# BMSMAX14921Based.net
KiCad netlist of a schematic drawn in EAGLE
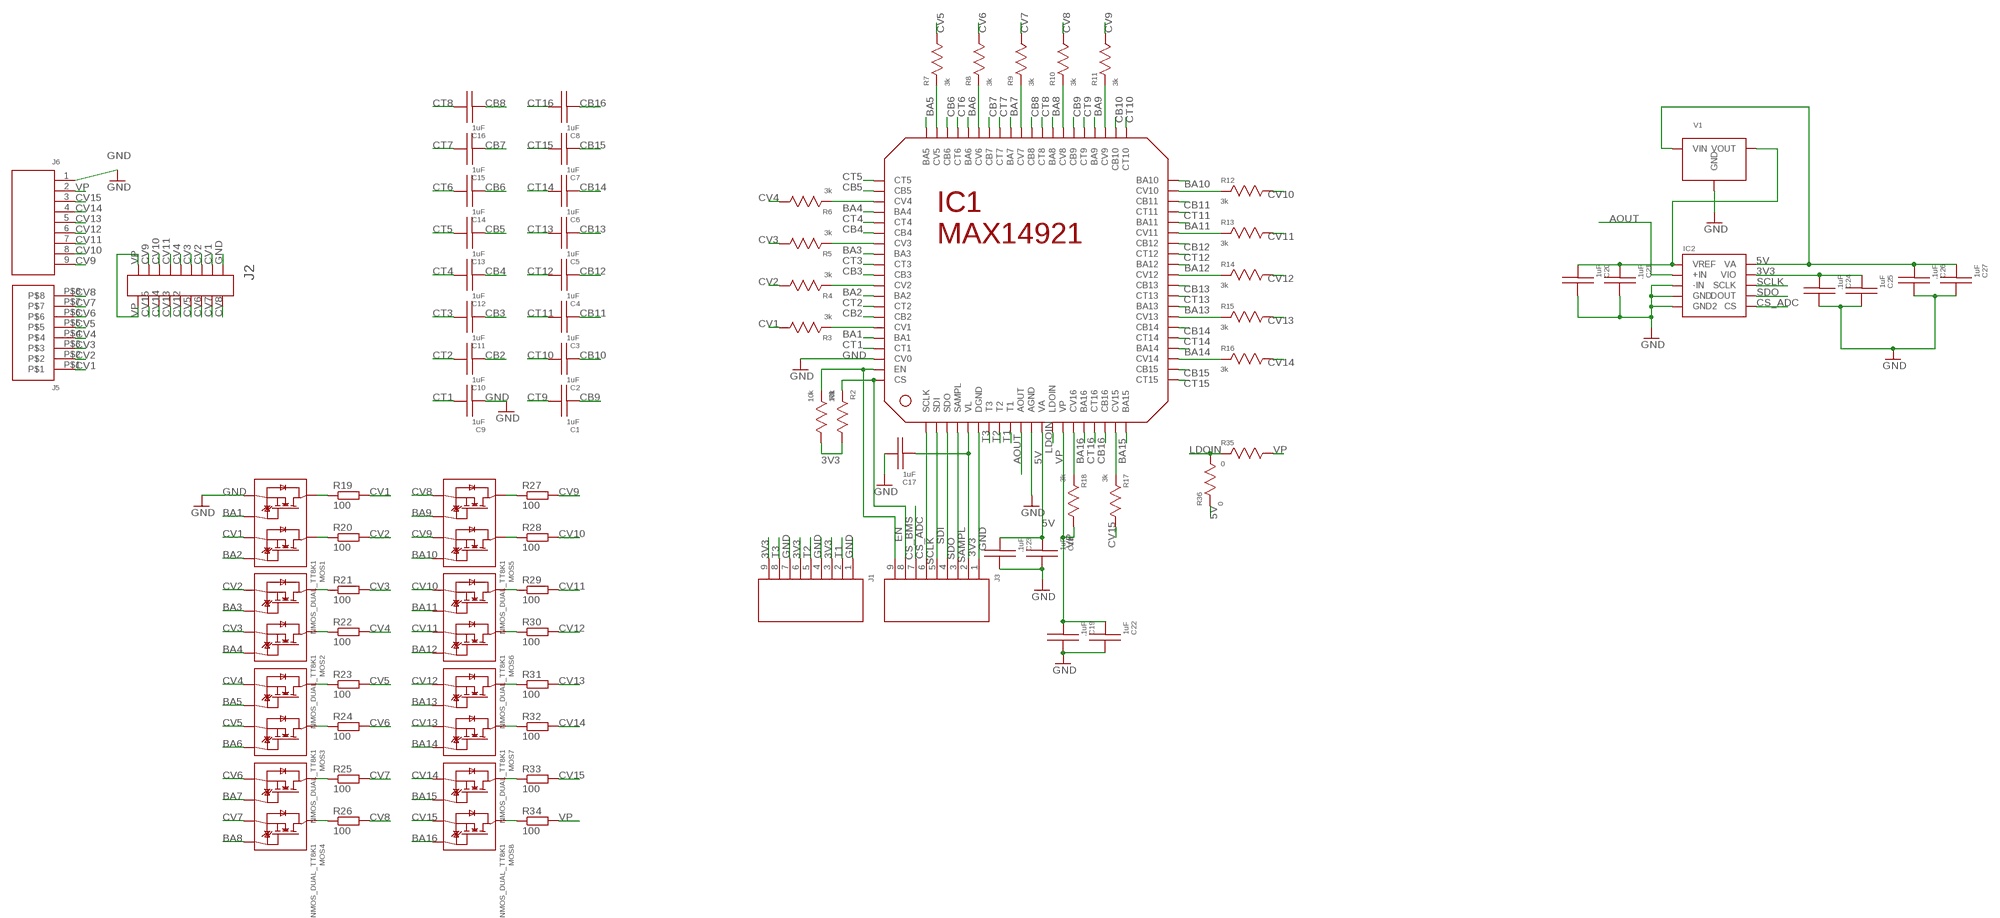
[diagram p0: schematic, sheet 1]

(export (version "E")
  (design (tool "Eeschema 10.0.6"))
  (components
    (comp (ref "C1")
      (value "1uF")
      (footprint "eagle-import:0805_(2012_METRIC)")
      (libsource (lib "eagle-import") (part "CHIP_CAP0805"))
    )
    (comp (ref "C2")
      (value "1uF")
      (footprint "eagle-import:0805_(2012_METRIC)")
      (libsource (lib "eagle-import") (part "CHIP_CAP0805"))
    )
    (comp (ref "C3")
      (value "1uF")
      (footprint "eagle-import:0805_(2012_METRIC)")
      (libsource (lib "eagle-import") (part "CHIP_CAP0805"))
    )
    (comp (ref "C4")
      (value "1uF")
      (footprint "eagle-import:0805_(2012_METRIC)")
      (libsource (lib "eagle-import") (part "CHIP_CAP0805"))
    )
    (comp (ref "C5")
      (value "1uF")
      (footprint "eagle-import:0805_(2012_METRIC)")
      (libsource (lib "eagle-import") (part "CHIP_CAP0805"))
    )
    (comp (ref "C6")
      (value "1uF")
      (footprint "eagle-import:0805_(2012_METRIC)")
      (libsource (lib "eagle-import") (part "CHIP_CAP0805"))
    )
    (comp (ref "C7")
      (value "1uF")
      (footprint "eagle-import:0805_(2012_METRIC)")
      (libsource (lib "eagle-import") (part "CHIP_CAP0805"))
    )
    (comp (ref "C8")
      (value "1uF")
      (footprint "eagle-import:0805_(2012_METRIC)")
      (libsource (lib "eagle-import") (part "CHIP_CAP0805"))
    )
    (comp (ref "C9")
      (value "1uF")
      (footprint "eagle-import:0805_(2012_METRIC)")
      (libsource (lib "eagle-import") (part "CHIP_CAP0805"))
    )
    (comp (ref "C10")
      (value "1uF")
      (footprint "eagle-import:0805_(2012_METRIC)")
      (libsource (lib "eagle-import") (part "CHIP_CAP0805"))
    )
    (comp (ref "C11")
      (value "1uF")
      (footprint "eagle-import:0805_(2012_METRIC)")
      (libsource (lib "eagle-import") (part "CHIP_CAP0805"))
    )
    (comp (ref "C12")
      (value "1uF")
      (footprint "eagle-import:0805_(2012_METRIC)")
      (libsource (lib "eagle-import") (part "CHIP_CAP0805"))
    )
    (comp (ref "C13")
      (value "1uF")
      (footprint "eagle-import:0805_(2012_METRIC)")
      (libsource (lib "eagle-import") (part "CHIP_CAP0805"))
    )
    (comp (ref "C14")
      (value "1uF")
      (footprint "eagle-import:0805_(2012_METRIC)")
      (libsource (lib "eagle-import") (part "CHIP_CAP0805"))
    )
    (comp (ref "C15")
      (value "1uF")
      (footprint "eagle-import:0805_(2012_METRIC)")
      (libsource (lib "eagle-import") (part "CHIP_CAP0805"))
    )
    (comp (ref "C16")
      (value "1uF")
      (footprint "eagle-import:0805_(2012_METRIC)")
      (libsource (lib "eagle-import") (part "CHIP_CAP0805"))
    )
    (comp (ref "C17")
      (value "1uF")
      (footprint "eagle-import:0805_(2012_METRIC)")
      (libsource (lib "eagle-import") (part "CHIP_CAP0805"))
    )
    (comp (ref "C18")
      (value "1uF")
      (footprint "eagle-import:0805_(2012_METRIC)")
      (libsource (lib "eagle-import") (part "CHIP_CAP0805"))
    )
    (comp (ref "C19")
      (value ".1uF")
      (footprint "eagle-import:0805_(2012_METRIC)")
      (libsource (lib "eagle-import") (part "CHIP_CAP0805"))
    )
    (comp (ref "C20")
      (value "1uF")
      (footprint "eagle-import:0805_(2012_METRIC)")
      (libsource (lib "eagle-import") (part "CHIP_CAP0805"))
    )
    (comp (ref "C21")
      (value ".1uF")
      (footprint "eagle-import:0805_(2012_METRIC)")
      (libsource (lib "eagle-import") (part "CHIP_CAP0805"))
    )
    (comp (ref "C22")
      (value "1uF")
      (footprint "eagle-import:0805_(2012_METRIC)")
      (libsource (lib "eagle-import") (part "CHIP_CAP0805"))
    )
    (comp (ref "C23")
      (value ".1uF")
      (footprint "eagle-import:0805_(2012_METRIC)")
      (libsource (lib "eagle-import") (part "CHIP_CAP0805"))
    )
    (comp (ref "C24")
      (value ".1uF")
      (footprint "eagle-import:0805_(2012_METRIC)")
      (libsource (lib "eagle-import") (part "CHIP_CAP0805"))
    )
    (comp (ref "C25")
      (value "1uF")
      (footprint "eagle-import:0805_(2012_METRIC)")
      (libsource (lib "eagle-import") (part "CHIP_CAP0805"))
    )
    (comp (ref "C26")
      (value ".1uF")
      (footprint "eagle-import:0805_(2012_METRIC)")
      (libsource (lib "eagle-import") (part "CHIP_CAP0805"))
    )
    (comp (ref "C27")
      (value "1uF")
      (footprint "eagle-import:0805_(2012_METRIC)")
      (libsource (lib "eagle-import") (part "CHIP_CAP0805"))
    )
    (comp (ref "IC1")
      (value "MAX14921")
      (footprint "eagle-import:80TQFP")
      (libsource (lib "eagle-import") (part "MAX14921"))
    )
    (comp (ref "IC2")
      (value "ADC141S626")
      (footprint "eagle-import:10-VSSOP")
      (libsource (lib "eagle-import") (part "ADC141S626"))
    )
    (comp (ref "J1")
      (value "CONNECTOR_9PIN")
      (footprint "eagle-import:9PIN_.1'")
      (libsource (lib "eagle-import") (part "CONNECTOR_9PIN"))
    )
    (comp (ref "J2")
      (value "CONNECTORJST2X9_2MM")
      (footprint "eagle-import:CONNECTOR9X2_2MMPITCH")
      (libsource (lib "eagle-import") (part "CONNECTORJST2X9_2MM"))
    )
    (comp (ref "J3")
      (value "CONNECTOR_9PIN")
      (footprint "eagle-import:9PIN_.1'")
      (libsource (lib "eagle-import") (part "CONNECTOR_9PIN"))
    )
    (comp (ref "J5")
      (value "CONNECTOR_8PIN")
      (footprint "eagle-import:8PIN_.1'")
      (libsource (lib "eagle-import") (part "CONNECTOR_8PIN"))
    )
    (comp (ref "J6")
      (value "CONNECTOR_9PIN")
      (footprint "eagle-import:9PIN_.1'")
      (libsource (lib "eagle-import") (part "CONNECTOR_9PIN"))
    )
    (comp (ref "MOS1")
      (value "NMOS_DUAL_TT8K1")
      (footprint "eagle-import:TSST8")
      (libsource (lib "eagle-import") (part "NMOS_DUAL_TT8K1"))
    )
    (comp (ref "MOS2")
      (value "NMOS_DUAL_TT8K1")
      (footprint "eagle-import:TSST8")
      (libsource (lib "eagle-import") (part "NMOS_DUAL_TT8K1"))
    )
    (comp (ref "MOS3")
      (value "NMOS_DUAL_TT8K1")
      (footprint "eagle-import:TSST8")
      (libsource (lib "eagle-import") (part "NMOS_DUAL_TT8K1"))
    )
    (comp (ref "MOS4")
      (value "NMOS_DUAL_TT8K1")
      (footprint "eagle-import:TSST8")
      (libsource (lib "eagle-import") (part "NMOS_DUAL_TT8K1"))
    )
    (comp (ref "MOS5")
      (value "NMOS_DUAL_TT8K1")
      (footprint "eagle-import:TSST8")
      (libsource (lib "eagle-import") (part "NMOS_DUAL_TT8K1"))
    )
    (comp (ref "MOS6")
      (value "NMOS_DUAL_TT8K1")
      (footprint "eagle-import:TSST8")
      (libsource (lib "eagle-import") (part "NMOS_DUAL_TT8K1"))
    )
    (comp (ref "MOS7")
      (value "NMOS_DUAL_TT8K1")
      (footprint "eagle-import:TSST8")
      (libsource (lib "eagle-import") (part "NMOS_DUAL_TT8K1"))
    )
    (comp (ref "MOS8")
      (value "NMOS_DUAL_TT8K1")
      (footprint "eagle-import:TSST8")
      (libsource (lib "eagle-import") (part "NMOS_DUAL_TT8K1"))
    )
    (comp (ref "R1")
      (value "10k")
      (footprint "eagle-import:0805_(2012_METRIC)")
      (libsource (lib "eagle-import") (part "CHIP_RES0805"))
    )
    (comp (ref "R2")
      (value "10k")
      (footprint "eagle-import:0805_(2012_METRIC)")
      (libsource (lib "eagle-import") (part "CHIP_RES0805"))
    )
    (comp (ref "R3")
      (value "3k")
      (footprint "eagle-import:0805_(2012_METRIC)")
      (libsource (lib "eagle-import") (part "CHIP_RES0805"))
    )
    (comp (ref "R4")
      (value "3k")
      (footprint "eagle-import:0805_(2012_METRIC)")
      (libsource (lib "eagle-import") (part "CHIP_RES0805"))
    )
    (comp (ref "R5")
      (value "3k")
      (footprint "eagle-import:0805_(2012_METRIC)")
      (libsource (lib "eagle-import") (part "CHIP_RES0805"))
    )
    (comp (ref "R6")
      (value "3k")
      (footprint "eagle-import:0805_(2012_METRIC)")
      (libsource (lib "eagle-import") (part "CHIP_RES0805"))
    )
    (comp (ref "R7")
      (value "3k")
      (footprint "eagle-import:0805_(2012_METRIC)")
      (libsource (lib "eagle-import") (part "CHIP_RES0805"))
    )
    (comp (ref "R8")
      (value "3k")
      (footprint "eagle-import:0805_(2012_METRIC)")
      (libsource (lib "eagle-import") (part "CHIP_RES0805"))
    )
    (comp (ref "R9")
      (value "3k")
      (footprint "eagle-import:0805_(2012_METRIC)")
      (libsource (lib "eagle-import") (part "CHIP_RES0805"))
    )
    (comp (ref "R10")
      (value "3k")
      (footprint "eagle-import:0805_(2012_METRIC)")
      (libsource (lib "eagle-import") (part "CHIP_RES0805"))
    )
    (comp (ref "R11")
      (value "3k")
      (footprint "eagle-import:0805_(2012_METRIC)")
      (libsource (lib "eagle-import") (part "CHIP_RES0805"))
    )
    (comp (ref "R12")
      (value "3k")
      (footprint "eagle-import:0805_(2012_METRIC)")
      (libsource (lib "eagle-import") (part "CHIP_RES0805"))
    )
    (comp (ref "R13")
      (value "3k")
      (footprint "eagle-import:0805_(2012_METRIC)")
      (libsource (lib "eagle-import") (part "CHIP_RES0805"))
    )
    (comp (ref "R14")
      (value "3k")
      (footprint "eagle-import:0805_(2012_METRIC)")
      (libsource (lib "eagle-import") (part "CHIP_RES0805"))
    )
    (comp (ref "R15")
      (value "3k")
      (footprint "eagle-import:0805_(2012_METRIC)")
      (libsource (lib "eagle-import") (part "CHIP_RES0805"))
    )
    (comp (ref "R16")
      (value "3k")
      (footprint "eagle-import:0805_(2012_METRIC)")
      (libsource (lib "eagle-import") (part "CHIP_RES0805"))
    )
    (comp (ref "R17")
      (value "3k")
      (footprint "eagle-import:0805_(2012_METRIC)")
      (libsource (lib "eagle-import") (part "CHIP_RES0805"))
    )
    (comp (ref "R18")
      (value "3k")
      (footprint "eagle-import:0805_(2012_METRIC)")
      (libsource (lib "eagle-import") (part "CHIP_RES0805"))
    )
    (comp (ref "R19")
      (value "100")
      (footprint "eagle-import:0411V")
      (libsource (lib "eagle-import") (part "R-EU_0411/3V"))
    )
    (comp (ref "R20")
      (value "100")
      (footprint "eagle-import:0411V")
      (libsource (lib "eagle-import") (part "R-EU_0411/3V"))
    )
    (comp (ref "R21")
      (value "100")
      (footprint "eagle-import:0411V")
      (libsource (lib "eagle-import") (part "R-EU_0411/3V"))
    )
    (comp (ref "R22")
      (value "100")
      (footprint "eagle-import:0411V")
      (libsource (lib "eagle-import") (part "R-EU_0411/3V"))
    )
    (comp (ref "R23")
      (value "100")
      (footprint "eagle-import:0411V")
      (libsource (lib "eagle-import") (part "R-EU_0411/3V"))
    )
    (comp (ref "R24")
      (value "100")
      (footprint "eagle-import:0411V")
      (libsource (lib "eagle-import") (part "R-EU_0411/3V"))
    )
    (comp (ref "R25")
      (value "100")
      (footprint "eagle-import:0411V")
      (libsource (lib "eagle-import") (part "R-EU_0411/3V"))
    )
    (comp (ref "R26")
      (value "100")
      (footprint "eagle-import:0411V")
      (libsource (lib "eagle-import") (part "R-EU_0411/3V"))
    )
    (comp (ref "R27")
      (value "100")
      (footprint "eagle-import:0411V")
      (libsource (lib "eagle-import") (part "R-EU_0411/3V"))
    )
    (comp (ref "R28")
      (value "100")
      (footprint "eagle-import:0411V")
      (libsource (lib "eagle-import") (part "R-EU_0411/3V"))
    )
    (comp (ref "R29")
      (value "100")
      (footprint "eagle-import:0411V")
      (libsource (lib "eagle-import") (part "R-EU_0411/3V"))
    )
    (comp (ref "R30")
      (value "100")
      (footprint "eagle-import:0411V")
      (libsource (lib "eagle-import") (part "R-EU_0411/3V"))
    )
    (comp (ref "R31")
      (value "100")
      (footprint "eagle-import:0411V")
      (libsource (lib "eagle-import") (part "R-EU_0411/3V"))
    )
    (comp (ref "R32")
      (value "100")
      (footprint "eagle-import:0411V")
      (libsource (lib "eagle-import") (part "R-EU_0411/3V"))
    )
    (comp (ref "R33")
      (value "100")
      (footprint "eagle-import:0411V")
      (libsource (lib "eagle-import") (part "R-EU_0411/3V"))
    )
    (comp (ref "R34")
      (value "100")
      (footprint "eagle-import:0411V")
      (libsource (lib "eagle-import") (part "R-EU_0411/3V"))
    )
    (comp (ref "R35")
      (value "0")
      (footprint "eagle-import:0805_(2012_METRIC)")
      (libsource (lib "eagle-import") (part "CHIP_RES0805"))
    )
    (comp (ref "R36")
      (value "0")
      (footprint "eagle-import:0805_(2012_METRIC)")
      (libsource (lib "eagle-import") (part "CHIP_RES0805"))
    )
    (comp (ref "V1")
      (value "REF3040")
      (footprint "eagle-import:SOT-23")
      (libsource (lib "eagle-import") (part "REF3040"))
    )
  )
  (nets
    (net (code "1") (name "/3V3") (class "Default")
      (node (ref "C17") (pin "P$2") (pinfunction "P$1_P$2") (pintype "bidirectional"))
      (node (ref "C24") (pin "P$2") (pinfunction "P$1_P$2") (pintype "bidirectional"))
      (node (ref "C25") (pin "P$2") (pinfunction "P$1_P$2") (pintype "bidirectional"))
      (node (ref "IC1") (pin "P$5") (pinfunction "VL_P$5") (pintype "bidirectional"))
      (node (ref "IC2") (pin "P$9") (pinfunction "VIO_P$9") (pintype "bidirectional"))
      (node (ref "J1") (pin "3") (pinfunction "P$3_3") (pintype "bidirectional"))
      (node (ref "J1") (pin "6") (pinfunction "P$6_6") (pintype "bidirectional"))
      (node (ref "J1") (pin "9") (pinfunction "P$9_9") (pintype "bidirectional"))
      (node (ref "J3") (pin "2") (pinfunction "P$2_2") (pintype "bidirectional"))
      (node (ref "R1") (pin "P$1") (pinfunction "P$2_P$1") (pintype "bidirectional"))
      (node (ref "R2") (pin "P$1") (pinfunction "P$2_P$1") (pintype "bidirectional"))
    )
    (net (code "2") (name "/5V") (class "Default")
      (node (ref "C18") (pin "P$2") (pinfunction "P$1_P$2") (pintype "bidirectional"))
      (node (ref "C23") (pin "P$2") (pinfunction "P$1_P$2") (pintype "bidirectional"))
      (node (ref "C26") (pin "P$2") (pinfunction "P$1_P$2") (pintype "bidirectional"))
      (node (ref "C27") (pin "P$2") (pinfunction "P$1_P$2") (pintype "bidirectional"))
      (node (ref "IC1") (pin "P$12") (pinfunction "VA_P$12") (pintype "bidirectional"))
      (node (ref "IC2") (pin "P$10") (pinfunction "VA_P$10") (pintype "bidirectional"))
      (node (ref "R36") (pin "P$2") (pinfunction "P$1_P$2") (pintype "bidirectional"))
      (node (ref "V1") (pin "1") (pinfunction "VIN_1") (pintype "bidirectional"))
    )
    (net (code "3") (name "/AOUT") (class "Default")
      (node (ref "IC1") (pin "P$10") (pinfunction "AOUT_P$10") (pintype "bidirectional"))
      (node (ref "IC2") (pin "P$2") (pinfunction "+IN_P$2") (pintype "bidirectional"))
    )
    (net (code "4") (name "/BA1") (class "Default")
      (node (ref "IC1") (pin "P$76") (pinfunction "BA1_P$76") (pintype "bidirectional"))
      (node (ref "MOS1") (pin "P$2") (pinfunction "G1_P$2") (pintype "bidirectional"))
    )
    (net (code "5") (name "/BA2") (class "Default")
      (node (ref "IC1") (pin "P$72") (pinfunction "BA2_P$72") (pintype "bidirectional"))
      (node (ref "MOS1") (pin "P$4") (pinfunction "G2_P$4") (pintype "bidirectional"))
    )
    (net (code "6") (name "/BA3") (class "Default")
      (node (ref "IC1") (pin "P$68") (pinfunction "BA3_P$68") (pintype "bidirectional"))
      (node (ref "MOS2") (pin "P$2") (pinfunction "G1_P$2") (pintype "bidirectional"))
    )
    (net (code "7") (name "/BA4") (class "Default")
      (node (ref "IC1") (pin "P$64") (pinfunction "BA4_P$64") (pintype "bidirectional"))
      (node (ref "MOS2") (pin "P$4") (pinfunction "G2_P$4") (pintype "bidirectional"))
    )
    (net (code "8") (name "/BA5") (class "Default")
      (node (ref "IC1") (pin "P$60") (pinfunction "BA5_P$60") (pintype "bidirectional"))
      (node (ref "MOS3") (pin "P$2") (pinfunction "G1_P$2") (pintype "bidirectional"))
    )
    (net (code "9") (name "/BA6") (class "Default")
      (node (ref "IC1") (pin "P$56") (pinfunction "BA6_P$56") (pintype "bidirectional"))
      (node (ref "MOS3") (pin "P$4") (pinfunction "G2_P$4") (pintype "bidirectional"))
    )
    (net (code "10") (name "/BA7") (class "Default")
      (node (ref "IC1") (pin "P$52") (pinfunction "BA7_P$52") (pintype "bidirectional"))
      (node (ref "MOS4") (pin "P$2") (pinfunction "G1_P$2") (pintype "bidirectional"))
    )
    (net (code "11") (name "/BA8") (class "Default")
      (node (ref "IC1") (pin "P$48") (pinfunction "BA8_P$48") (pintype "bidirectional"))
      (node (ref "MOS4") (pin "P$4") (pinfunction "G2_P$4") (pintype "bidirectional"))
    )
    (net (code "12") (name "/BA9") (class "Default")
      (node (ref "IC1") (pin "P$44") (pinfunction "BA9_P$44") (pintype "bidirectional"))
      (node (ref "MOS5") (pin "P$2") (pinfunction "G1_P$2") (pintype "bidirectional"))
    )
    (net (code "13") (name "/BA10") (class "Default")
      (node (ref "IC1") (pin "P$40") (pinfunction "BA10_P$40") (pintype "bidirectional"))
      (node (ref "MOS5") (pin "P$4") (pinfunction "G2_P$4") (pintype "bidirectional"))
    )
    (net (code "14") (name "/BA11") (class "Default")
      (node (ref "IC1") (pin "P$36") (pinfunction "BA11_P$36") (pintype "bidirectional"))
      (node (ref "MOS6") (pin "P$2") (pinfunction "G1_P$2") (pintype "bidirectional"))
    )
    (net (code "15") (name "/BA12") (class "Default")
      (node (ref "IC1") (pin "P$32") (pinfunction "BA12_P$32") (pintype "bidirectional"))
      (node (ref "MOS6") (pin "P$4") (pinfunction "G2_P$4") (pintype "bidirectional"))
    )
    (net (code "16") (name "/BA13") (class "Default")
      (node (ref "IC1") (pin "P$28") (pinfunction "BA13_P$28") (pintype "bidirectional"))
      (node (ref "MOS7") (pin "P$2") (pinfunction "G1_P$2") (pintype "bidirectional"))
    )
    (net (code "17") (name "/BA14") (class "Default")
      (node (ref "IC1") (pin "P$24") (pinfunction "BA14_P$24") (pintype "bidirectional"))
      (node (ref "MOS7") (pin "P$4") (pinfunction "G2_P$4") (pintype "bidirectional"))
    )
    (net (code "18") (name "/BA15") (class "Default")
      (node (ref "IC1") (pin "P$20") (pinfunction "BA15_P$20") (pintype "bidirectional"))
      (node (ref "MOS8") (pin "P$2") (pinfunction "G1_P$2") (pintype "bidirectional"))
    )
    (net (code "19") (name "/BA16") (class "Default")
      (node (ref "IC1") (pin "P$16") (pinfunction "BA16_P$16") (pintype "bidirectional"))
      (node (ref "MOS8") (pin "P$4") (pinfunction "G2_P$4") (pintype "bidirectional"))
    )
    (net (code "20") (name "/CB2") (class "Default")
      (node (ref "C10") (pin "P$2") (pinfunction "P$1_P$2") (pintype "bidirectional"))
      (node (ref "IC1") (pin "P$74") (pinfunction "CB2_P$74") (pintype "bidirectional"))
    )
    (net (code "21") (name "/CB3") (class "Default")
      (node (ref "C11") (pin "P$2") (pinfunction "P$1_P$2") (pintype "bidirectional"))
      (node (ref "IC1") (pin "P$70") (pinfunction "CB3_P$70") (pintype "bidirectional"))
    )
    (net (code "22") (name "/CB4") (class "Default")
      (node (ref "C12") (pin "P$2") (pinfunction "P$1_P$2") (pintype "bidirectional"))
      (node (ref "IC1") (pin "P$66") (pinfunction "CB4_P$66") (pintype "bidirectional"))
    )
    (net (code "23") (name "/CB5") (class "Default")
      (node (ref "C13") (pin "P$2") (pinfunction "P$1_P$2") (pintype "bidirectional"))
      (node (ref "IC1") (pin "P$62") (pinfunction "CB5_P$62") (pintype "bidirectional"))
    )
    (net (code "24") (name "/CB6") (class "Default")
      (node (ref "C14") (pin "P$2") (pinfunction "P$1_P$2") (pintype "bidirectional"))
      (node (ref "IC1") (pin "P$58") (pinfunction "CB6_P$58") (pintype "bidirectional"))
    )
    (net (code "25") (name "/CB7") (class "Default")
      (node (ref "C15") (pin "P$2") (pinfunction "P$1_P$2") (pintype "bidirectional"))
      (node (ref "IC1") (pin "P$54") (pinfunction "CB7_P$54") (pintype "bidirectional"))
    )
    (net (code "26") (name "/CB8") (class "Default")
      (node (ref "C16") (pin "P$2") (pinfunction "P$1_P$2") (pintype "bidirectional"))
      (node (ref "IC1") (pin "P$50") (pinfunction "CB8_P$50") (pintype "bidirectional"))
    )
    (net (code "27") (name "/CB9") (class "Default")
      (node (ref "C1") (pin "P$2") (pinfunction "P$1_P$2") (pintype "bidirectional"))
      (node (ref "IC1") (pin "P$46") (pinfunction "CB9_P$46") (pintype "bidirectional"))
    )
    (net (code "28") (name "/CB10") (class "Default")
      (node (ref "C2") (pin "P$2") (pinfunction "P$1_P$2") (pintype "bidirectional"))
      (node (ref "IC1") (pin "P$42") (pinfunction "CB10_P$42") (pintype "bidirectional"))
    )
    (net (code "29") (name "/CB11") (class "Default")
      (node (ref "C3") (pin "P$2") (pinfunction "P$1_P$2") (pintype "bidirectional"))
      (node (ref "IC1") (pin "P$38") (pinfunction "CB11_P$38") (pintype "bidirectional"))
    )
    (net (code "30") (name "/CB12") (class "Default")
      (node (ref "C4") (pin "P$2") (pinfunction "P$1_P$2") (pintype "bidirectional"))
      (node (ref "IC1") (pin "P$34") (pinfunction "CB12_P$34") (pintype "bidirectional"))
    )
    (net (code "31") (name "/CB13") (class "Default")
      (node (ref "C5") (pin "P$2") (pinfunction "P$1_P$2") (pintype "bidirectional"))
      (node (ref "IC1") (pin "P$30") (pinfunction "CB13_P$30") (pintype "bidirectional"))
    )
    (net (code "32") (name "/CB14") (class "Default")
      (node (ref "C6") (pin "P$2") (pinfunction "P$1_P$2") (pintype "bidirectional"))
      (node (ref "IC1") (pin "P$26") (pinfunction "CB14_P$26") (pintype "bidirectional"))
    )
    (net (code "33") (name "/CB15") (class "Default")
      (node (ref "C7") (pin "P$2") (pinfunction "P$1_P$2") (pintype "bidirectional"))
      (node (ref "IC1") (pin "P$22") (pinfunction "CB15_P$22") (pintype "bidirectional"))
    )
    (net (code "34") (name "/CB16") (class "Default")
      (node (ref "C8") (pin "P$2") (pinfunction "P$1_P$2") (pintype "bidirectional"))
      (node (ref "IC1") (pin "P$18") (pinfunction "CB16_P$18") (pintype "bidirectional"))
    )
    (net (code "35") (name "/CS_ADC") (class "Default")
      (node (ref "IC2") (pin "P$6") (pinfunction "CS_P$6") (pintype "bidirectional"))
      (node (ref "J3") (pin "7") (pinfunction "P$7_7") (pintype "bidirectional"))
    )
    (net (code "36") (name "/CS_BMS") (class "Default")
      (node (ref "IC1") (pin "P$80") (pinfunction "CS_P$80") (pintype "bidirectional"))
      (node (ref "J3") (pin "8") (pinfunction "P$8_8") (pintype "bidirectional"))
      (node (ref "R2") (pin "P$2") (pinfunction "P$1_P$2") (pintype "bidirectional"))
    )
    (net (code "37") (name "/CT1") (class "Default")
      (node (ref "C9") (pin "P$1") (pinfunction "P$2_P$1") (pintype "bidirectional"))
      (node (ref "IC1") (pin "P$77") (pinfunction "CT1_P$77") (pintype "bidirectional"))
    )
    (net (code "38") (name "/CT2") (class "Default")
      (node (ref "C10") (pin "P$1") (pinfunction "P$2_P$1") (pintype "bidirectional"))
      (node (ref "IC1") (pin "P$73") (pinfunction "CT2_P$73") (pintype "bidirectional"))
    )
    (net (code "39") (name "/CT3") (class "Default")
      (node (ref "C11") (pin "P$1") (pinfunction "P$2_P$1") (pintype "bidirectional"))
      (node (ref "IC1") (pin "P$69") (pinfunction "CT3_P$69") (pintype "bidirectional"))
    )
    (net (code "40") (name "/CT4") (class "Default")
      (node (ref "C12") (pin "P$1") (pinfunction "P$2_P$1") (pintype "bidirectional"))
      (node (ref "IC1") (pin "P$65") (pinfunction "CT4_P$65") (pintype "bidirectional"))
    )
    (net (code "41") (name "/CT5") (class "Default")
      (node (ref "C13") (pin "P$1") (pinfunction "P$2_P$1") (pintype "bidirectional"))
      (node (ref "IC1") (pin "P$61") (pinfunction "CT5_P$61") (pintype "bidirectional"))
    )
    (net (code "42") (name "/CT6") (class "Default")
      (node (ref "C14") (pin "P$1") (pinfunction "P$2_P$1") (pintype "bidirectional"))
      (node (ref "IC1") (pin "P$57") (pinfunction "CT6_P$57") (pintype "bidirectional"))
    )
    (net (code "43") (name "/CT7") (class "Default")
      (node (ref "C15") (pin "P$1") (pinfunction "P$2_P$1") (pintype "bidirectional"))
      (node (ref "IC1") (pin "P$53") (pinfunction "CT7_P$53") (pintype "bidirectional"))
    )
    (net (code "44") (name "/CT8") (class "Default")
      (node (ref "C16") (pin "P$1") (pinfunction "P$2_P$1") (pintype "bidirectional"))
      (node (ref "IC1") (pin "P$49") (pinfunction "CT8_P$49") (pintype "bidirectional"))
    )
    (net (code "45") (name "/CT9") (class "Default")
      (node (ref "C1") (pin "P$1") (pinfunction "P$2_P$1") (pintype "bidirectional"))
      (node (ref "IC1") (pin "P$45") (pinfunction "CT9_P$45") (pintype "bidirectional"))
    )
    (net (code "46") (name "/CT10") (class "Default")
      (node (ref "C2") (pin "P$1") (pinfunction "P$2_P$1") (pintype "bidirectional"))
      (node (ref "IC1") (pin "P$41") (pinfunction "CT10_P$41") (pintype "bidirectional"))
    )
    (net (code "47") (name "/CT11") (class "Default")
      (node (ref "C3") (pin "P$1") (pinfunction "P$2_P$1") (pintype "bidirectional"))
      (node (ref "IC1") (pin "P$37") (pinfunction "CT11_P$37") (pintype "bidirectional"))
    )
    (net (code "48") (name "/CT12") (class "Default")
      (node (ref "C4") (pin "P$1") (pinfunction "P$2_P$1") (pintype "bidirectional"))
      (node (ref "IC1") (pin "P$33") (pinfunction "CT12_P$33") (pintype "bidirectional"))
    )
    (net (code "49") (name "/CT13") (class "Default")
      (node (ref "C5") (pin "P$1") (pinfunction "P$2_P$1") (pintype "bidirectional"))
      (node (ref "IC1") (pin "P$29") (pinfunction "CT13_P$29") (pintype "bidirectional"))
    )
    (net (code "50") (name "/CT14") (class "Default")
      (node (ref "C6") (pin "P$1") (pinfunction "P$2_P$1") (pintype "bidirectional"))
      (node (ref "IC1") (pin "P$25") (pinfunction "CT14_P$25") (pintype "bidirectional"))
    )
    (net (code "51") (name "/CT15") (class "Default")
      (node (ref "C7") (pin "P$1") (pinfunction "P$2_P$1") (pintype "bidirectional"))
      (node (ref "IC1") (pin "P$21") (pinfunction "CT15_P$21") (pintype "bidirectional"))
    )
    (net (code "52") (name "/CT16") (class "Default")
      (node (ref "C8") (pin "P$1") (pinfunction "P$2_P$1") (pintype "bidirectional"))
      (node (ref "IC1") (pin "P$17") (pinfunction "CT16_P$17") (pintype "bidirectional"))
    )
    (net (code "53") (name "/CV1") (class "Default")
      (node (ref "J2") (pin "P$2") (pinfunction "P$2_P$2") (pintype "bidirectional"))
      (node (ref "J5") (pin "P$1") (pinfunction "P$1_P$1") (pintype "bidirectional"))
      (node (ref "MOS1") (pin "P$3") (pinfunction "S2_P$3") (pintype "bidirectional"))
      (node (ref "R19") (pin "2") (pinfunction "2_2") (pintype "passive"))
      (node (ref "R3") (pin "P$1") (pinfunction "P$2_P$1") (pintype "bidirectional"))
    )
    (net (code "54") (name "/CV2") (class "Default")
      (node (ref "J2") (pin "P$3") (pinfunction "P$3_P$3") (pintype "bidirectional"))
      (node (ref "J5") (pin "P$2") (pinfunction "P$2_P$2") (pintype "bidirectional"))
      (node (ref "MOS2") (pin "P$1") (pinfunction "S1_P$1") (pintype "bidirectional"))
      (node (ref "R20") (pin "2") (pinfunction "2_2") (pintype "passive"))
      (node (ref "R4") (pin "P$1") (pinfunction "P$2_P$1") (pintype "bidirectional"))
    )
    (net (code "55") (name "/CV3") (class "Default")
      (node (ref "J2") (pin "P$4") (pinfunction "P$4_P$4") (pintype "bidirectional"))
      (node (ref "J5") (pin "P$3") (pinfunction "P$3_P$3") (pintype "bidirectional"))
      (node (ref "MOS2") (pin "P$3") (pinfunction "S2_P$3") (pintype "bidirectional"))
      (node (ref "R21") (pin "2") (pinfunction "2_2") (pintype "passive"))
      (node (ref "R5") (pin "P$1") (pinfunction "P$2_P$1") (pintype "bidirectional"))
    )
    (net (code "56") (name "/CV4") (class "Default")
      (node (ref "J2") (pin "P$5") (pinfunction "P$5_P$5") (pintype "bidirectional"))
      (node (ref "J5") (pin "P$4") (pinfunction "P$4_P$4") (pintype "bidirectional"))
      (node (ref "MOS3") (pin "P$1") (pinfunction "S1_P$1") (pintype "bidirectional"))
      (node (ref "R22") (pin "2") (pinfunction "2_2") (pintype "passive"))
      (node (ref "R6") (pin "P$1") (pinfunction "P$2_P$1") (pintype "bidirectional"))
    )
    (net (code "57") (name "/CV5") (class "Default")
      (node (ref "J2") (pin "P$15") (pinfunction "P$15_P$15") (pintype "bidirectional"))
      (node (ref "J5") (pin "P$5") (pinfunction "P$5_P$5") (pintype "bidirectional"))
      (node (ref "MOS3") (pin "P$3") (pinfunction "S2_P$3") (pintype "bidirectional"))
      (node (ref "R23") (pin "2") (pinfunction "2_2") (pintype "passive"))
      (node (ref "R7") (pin "P$1") (pinfunction "P$2_P$1") (pintype "bidirectional"))
    )
    (net (code "58") (name "/CV6") (class "Default")
      (node (ref "J2") (pin "P$16") (pinfunction "P$16_P$16") (pintype "bidirectional"))
      (node (ref "J5") (pin "P$6") (pinfunction "P$6_P$6") (pintype "bidirectional"))
      (node (ref "MOS4") (pin "P$1") (pinfunction "S1_P$1") (pintype "bidirectional"))
      (node (ref "R24") (pin "2") (pinfunction "2_2") (pintype "passive"))
      (node (ref "R8") (pin "P$1") (pinfunction "P$2_P$1") (pintype "bidirectional"))
    )
    (net (code "59") (name "/CV7") (class "Default")
      (node (ref "J2") (pin "P$17") (pinfunction "P$17_P$17") (pintype "bidirectional"))
      (node (ref "J5") (pin "P$7") (pinfunction "P$7_P$7") (pintype "bidirectional"))
      (node (ref "MOS4") (pin "P$3") (pinfunction "S2_P$3") (pintype "bidirectional"))
      (node (ref "R25") (pin "2") (pinfunction "2_2") (pintype "passive"))
      (node (ref "R9") (pin "P$1") (pinfunction "P$2_P$1") (pintype "bidirectional"))
    )
    (net (code "60") (name "/CV8") (class "Default")
      (node (ref "J2") (pin "P$18") (pinfunction "P$18_P$18") (pintype "bidirectional"))
      (node (ref "J5") (pin "P$8") (pinfunction "P$8_P$8") (pintype "bidirectional"))
      (node (ref "MOS5") (pin "P$1") (pinfunction "S1_P$1") (pintype "bidirectional"))
      (node (ref "R10") (pin "P$1") (pinfunction "P$2_P$1") (pintype "bidirectional"))
      (node (ref "R26") (pin "2") (pinfunction "2_2") (pintype "passive"))
    )
    (net (code "61") (name "/CV9") (class "Default")
      (node (ref "J2") (pin "P$8") (pinfunction "P$8_P$8") (pintype "bidirectional"))
      (node (ref "J6") (pin "9") (pinfunction "P$9_9") (pintype "bidirectional"))
      (node (ref "MOS5") (pin "P$3") (pinfunction "S2_P$3") (pintype "bidirectional"))
      (node (ref "R11") (pin "P$1") (pinfunction "P$2_P$1") (pintype "bidirectional"))
      (node (ref "R27") (pin "2") (pinfunction "2_2") (pintype "passive"))
    )
    (net (code "62") (name "/CV10") (class "Default")
      (node (ref "J2") (pin "P$7") (pinfunction "P$7_P$7") (pintype "bidirectional"))
      (node (ref "J6") (pin "8") (pinfunction "P$8_8") (pintype "bidirectional"))
      (node (ref "MOS6") (pin "P$1") (pinfunction "S1_P$1") (pintype "bidirectional"))
      (node (ref "R12") (pin "P$1") (pinfunction "P$2_P$1") (pintype "bidirectional"))
      (node (ref "R28") (pin "2") (pinfunction "2_2") (pintype "passive"))
    )
    (net (code "63") (name "/CV11") (class "Default")
      (node (ref "J2") (pin "P$6") (pinfunction "P$6_P$6") (pintype "bidirectional"))
      (node (ref "J6") (pin "7") (pinfunction "P$7_7") (pintype "bidirectional"))
      (node (ref "MOS6") (pin "P$3") (pinfunction "S2_P$3") (pintype "bidirectional"))
      (node (ref "R13") (pin "P$1") (pinfunction "P$2_P$1") (pintype "bidirectional"))
      (node (ref "R29") (pin "2") (pinfunction "2_2") (pintype "passive"))
    )
    (net (code "64") (name "/CV12") (class "Default")
      (node (ref "J2") (pin "P$14") (pinfunction "P$14_P$14") (pintype "bidirectional"))
      (node (ref "J6") (pin "6") (pinfunction "P$6_6") (pintype "bidirectional"))
      (node (ref "MOS7") (pin "P$1") (pinfunction "S1_P$1") (pintype "bidirectional"))
      (node (ref "R14") (pin "P$1") (pinfunction "P$2_P$1") (pintype "bidirectional"))
      (node (ref "R30") (pin "2") (pinfunction "2_2") (pintype "passive"))
    )
    (net (code "65") (name "/CV13") (class "Default")
      (node (ref "J2") (pin "P$13") (pinfunction "P$13_P$13") (pintype "bidirectional"))
      (node (ref "J6") (pin "5") (pinfunction "P$5_5") (pintype "bidirectional"))
      (node (ref "MOS7") (pin "P$3") (pinfunction "S2_P$3") (pintype "bidirectional"))
      (node (ref "R15") (pin "P$1") (pinfunction "P$2_P$1") (pintype "bidirectional"))
      (node (ref "R31") (pin "2") (pinfunction "2_2") (pintype "passive"))
    )
    (net (code "66") (name "/CV14") (class "Default")
      (node (ref "J2") (pin "P$12") (pinfunction "P$12_P$12") (pintype "bidirectional"))
      (node (ref "J6") (pin "4") (pinfunction "P$4_4") (pintype "bidirectional"))
      (node (ref "MOS8") (pin "P$1") (pinfunction "S1_P$1") (pintype "bidirectional"))
      (node (ref "R16") (pin "P$1") (pinfunction "P$2_P$1") (pintype "bidirectional"))
      (node (ref "R32") (pin "2") (pinfunction "2_2") (pintype "passive"))
    )
    (net (code "67") (name "/CV15") (class "Default")
      (node (ref "J2") (pin "P$11") (pinfunction "P$11_P$11") (pintype "bidirectional"))
      (node (ref "J6") (pin "3") (pinfunction "P$3_3") (pintype "bidirectional"))
      (node (ref "MOS8") (pin "P$3") (pinfunction "S2_P$3") (pintype "bidirectional"))
      (node (ref "R17") (pin "P$1") (pinfunction "P$2_P$1") (pintype "bidirectional"))
      (node (ref "R33") (pin "2") (pinfunction "2_2") (pintype "passive"))
    )
    (net (code "68") (name "/EN") (class "Default")
      (node (ref "IC1") (pin "P$79") (pinfunction "EN_P$79") (pintype "bidirectional"))
      (node (ref "J3") (pin "9") (pinfunction "P$9_9") (pintype "bidirectional"))
      (node (ref "R1") (pin "P$2") (pinfunction "P$1_P$2") (pintype "bidirectional"))
    )
    (net (code "69") (name "/LDOIN") (class "Default")
      (node (ref "IC1") (pin "P$13") (pinfunction "LDOIN_P$13") (pintype "bidirectional"))
      (node (ref "R35") (pin "P$2") (pinfunction "P$1_P$2") (pintype "bidirectional"))
      (node (ref "R36") (pin "P$1") (pinfunction "P$2_P$1") (pintype "bidirectional"))
    )
    (net (code "70") (name "/SAMPL") (class "Default")
      (node (ref "IC1") (pin "P$4") (pinfunction "SAMPL_P$4") (pintype "bidirectional"))
      (node (ref "J3") (pin "3") (pinfunction "P$3_3") (pintype "bidirectional"))
    )
    (net (code "71") (name "/SCLK") (class "Default")
      (node (ref "IC1") (pin "P$1") (pinfunction "SCLK_P$1") (pintype "bidirectional"))
      (node (ref "IC2") (pin "P$8") (pinfunction "SCLK_P$8") (pintype "bidirectional"))
      (node (ref "J3") (pin "6") (pinfunction "P$6_6") (pintype "bidirectional"))
    )
    (net (code "72") (name "/SDI") (class "Default")
      (node (ref "IC1") (pin "P$2") (pinfunction "SDI_P$2") (pintype "bidirectional"))
      (node (ref "J3") (pin "5") (pinfunction "P$5_5") (pintype "bidirectional"))
    )
    (net (code "73") (name "/SDO") (class "Default")
      (node (ref "IC1") (pin "P$3") (pinfunction "SDO_P$3") (pintype "bidirectional"))
      (node (ref "IC2") (pin "P$7") (pinfunction "DOUT_P$7") (pintype "bidirectional"))
      (node (ref "J3") (pin "4") (pinfunction "P$4_4") (pintype "bidirectional"))
    )
    (net (code "74") (name "/T1") (class "Default")
      (node (ref "IC1") (pin "P$9") (pinfunction "T1_P$9") (pintype "bidirectional"))
      (node (ref "J1") (pin "2") (pinfunction "P$2_2") (pintype "bidirectional"))
    )
    (net (code "75") (name "/T2") (class "Default")
      (node (ref "IC1") (pin "P$8") (pinfunction "T2_P$8") (pintype "bidirectional"))
      (node (ref "J1") (pin "5") (pinfunction "P$5_5") (pintype "bidirectional"))
    )
    (net (code "76") (name "/T3") (class "Default")
      (node (ref "IC1") (pin "P$7") (pinfunction "T3_P$7") (pintype "bidirectional"))
      (node (ref "J1") (pin "8") (pinfunction "P$8_8") (pintype "bidirectional"))
    )
    (net (code "77") (name "/VP") (class "Default")
      (node (ref "C19") (pin "P$2") (pinfunction "P$1_P$2") (pintype "bidirectional"))
      (node (ref "C22") (pin "P$2") (pinfunction "P$1_P$2") (pintype "bidirectional"))
      (node (ref "IC1") (pin "P$14") (pinfunction "VP_P$14") (pintype "bidirectional"))
      (node (ref "J2") (pin "P$10") (pinfunction "P$10_P$10") (pintype "bidirectional"))
      (node (ref "J2") (pin "P$9") (pinfunction "P$9_P$9") (pintype "bidirectional"))
      (node (ref "J6") (pin "2") (pinfunction "P$2_2") (pintype "bidirectional"))
      (node (ref "R18") (pin "P$1") (pinfunction "P$2_P$1") (pintype "bidirectional"))
      (node (ref "R34") (pin "2") (pinfunction "2_2") (pintype "passive"))
      (node (ref "R35") (pin "P$1") (pinfunction "P$2_P$1") (pintype "bidirectional"))
    )
    (net (code "78") (name "GND") (class "Default")
      (node (ref "C17") (pin "P$1") (pinfunction "P$2_P$1") (pintype "bidirectional"))
      (node (ref "C18") (pin "P$1") (pinfunction "P$2_P$1") (pintype "bidirectional"))
      (node (ref "C19") (pin "P$1") (pinfunction "P$2_P$1") (pintype "bidirectional"))
      (node (ref "C20") (pin "P$1") (pinfunction "P$2_P$1") (pintype "bidirectional"))
      (node (ref "C21") (pin "P$1") (pinfunction "P$2_P$1") (pintype "bidirectional"))
      (node (ref "C22") (pin "P$1") (pinfunction "P$2_P$1") (pintype "bidirectional"))
      (node (ref "C23") (pin "P$1") (pinfunction "P$2_P$1") (pintype "bidirectional"))
      (node (ref "C24") (pin "P$1") (pinfunction "P$2_P$1") (pintype "bidirectional"))
      (node (ref "C25") (pin "P$1") (pinfunction "P$2_P$1") (pintype "bidirectional"))
      (node (ref "C26") (pin "P$1") (pinfunction "P$2_P$1") (pintype "bidirectional"))
      (node (ref "C27") (pin "P$1") (pinfunction "P$2_P$1") (pintype "bidirectional"))
      (node (ref "C9") (pin "P$2") (pinfunction "P$1_P$2") (pintype "bidirectional"))
      (node (ref "IC1") (pin "P$11") (pinfunction "AGND_P$11") (pintype "bidirectional"))
      (node (ref "IC1") (pin "P$6") (pinfunction "DGND_P$6") (pintype "bidirectional"))
      (node (ref "IC1") (pin "P$78") (pinfunction "CV0_P$78") (pintype "bidirectional"))
      (node (ref "IC2") (pin "P$3") (pinfunction "-IN_P$3") (pintype "bidirectional"))
      (node (ref "IC2") (pin "P$4") (pinfunction "GND_P$4") (pintype "bidirectional"))
      (node (ref "IC2") (pin "P$5") (pinfunction "GND2_P$5") (pintype "bidirectional"))
      (node (ref "J1") (pin "1") (pinfunction "P$1_1") (pintype "bidirectional"))
      (node (ref "J1") (pin "4") (pinfunction "P$4_4") (pintype "bidirectional"))
      (node (ref "J1") (pin "7") (pinfunction "P$7_7") (pintype "bidirectional"))
      (node (ref "J2") (pin "P$1") (pinfunction "P$1_P$1") (pintype "bidirectional"))
      (node (ref "J3") (pin "1") (pinfunction "P$1_1") (pintype "bidirectional"))
      (node (ref "J6") (pin "1") (pinfunction "P$1_1") (pintype "bidirectional"))
      (node (ref "MOS1") (pin "P$1") (pinfunction "S1_P$1") (pintype "bidirectional"))
      (node (ref "V1") (pin "3") (pinfunction "GND_3") (pintype "bidirectional"))
    )
    (net (code "79") (name "Net-(C20-P$1)") (class "Default")
      (node (ref "C20") (pin "P$2") (pinfunction "P$1_P$2") (pintype "bidirectional"))
      (node (ref "C21") (pin "P$2") (pinfunction "P$1_P$2") (pintype "bidirectional"))
      (node (ref "IC2") (pin "P$1") (pinfunction "VREF_P$1") (pintype "bidirectional"))
      (node (ref "V1") (pin "2") (pinfunction "VOUT_2") (pintype "bidirectional"))
    )
    (net (code "80") (name "Net-(IC1-CV1)") (class "Default")
      (node (ref "IC1") (pin "P$75") (pinfunction "CV1_P$75") (pintype "bidirectional"))
      (node (ref "R3") (pin "P$2") (pinfunction "P$1_P$2") (pintype "bidirectional"))
    )
    (net (code "81") (name "Net-(IC1-CV2)") (class "Default")
      (node (ref "IC1") (pin "P$71") (pinfunction "CV2_P$71") (pintype "bidirectional"))
      (node (ref "R4") (pin "P$2") (pinfunction "P$1_P$2") (pintype "bidirectional"))
    )
    (net (code "82") (name "Net-(IC1-CV3)") (class "Default")
      (node (ref "IC1") (pin "P$67") (pinfunction "CV3_P$67") (pintype "bidirectional"))
      (node (ref "R5") (pin "P$2") (pinfunction "P$1_P$2") (pintype "bidirectional"))
    )
    (net (code "83") (name "Net-(IC1-CV4)") (class "Default")
      (node (ref "IC1") (pin "P$63") (pinfunction "CV4_P$63") (pintype "bidirectional"))
      (node (ref "R6") (pin "P$2") (pinfunction "P$1_P$2") (pintype "bidirectional"))
    )
    (net (code "84") (name "Net-(IC1-CV5)") (class "Default")
      (node (ref "IC1") (pin "P$59") (pinfunction "CV5_P$59") (pintype "bidirectional"))
      (node (ref "R7") (pin "P$2") (pinfunction "P$1_P$2") (pintype "bidirectional"))
    )
    (net (code "85") (name "Net-(IC1-CV6)") (class "Default")
      (node (ref "IC1") (pin "P$55") (pinfunction "CV6_P$55") (pintype "bidirectional"))
      (node (ref "R8") (pin "P$2") (pinfunction "P$1_P$2") (pintype "bidirectional"))
    )
    (net (code "86") (name "Net-(IC1-CV7)") (class "Default")
      (node (ref "IC1") (pin "P$51") (pinfunction "CV7_P$51") (pintype "bidirectional"))
      (node (ref "R9") (pin "P$2") (pinfunction "P$1_P$2") (pintype "bidirectional"))
    )
    (net (code "87") (name "Net-(IC1-CV8)") (class "Default")
      (node (ref "IC1") (pin "P$47") (pinfunction "CV8_P$47") (pintype "bidirectional"))
      (node (ref "R10") (pin "P$2") (pinfunction "P$1_P$2") (pintype "bidirectional"))
    )
    (net (code "88") (name "Net-(IC1-CV9)") (class "Default")
      (node (ref "IC1") (pin "P$43") (pinfunction "CV9_P$43") (pintype "bidirectional"))
      (node (ref "R11") (pin "P$2") (pinfunction "P$1_P$2") (pintype "bidirectional"))
    )
    (net (code "89") (name "Net-(IC1-CV10)") (class "Default")
      (node (ref "IC1") (pin "P$39") (pinfunction "CV10_P$39") (pintype "bidirectional"))
      (node (ref "R12") (pin "P$2") (pinfunction "P$1_P$2") (pintype "bidirectional"))
    )
    (net (code "90") (name "Net-(IC1-CV11)") (class "Default")
      (node (ref "IC1") (pin "P$35") (pinfunction "CV11_P$35") (pintype "bidirectional"))
      (node (ref "R13") (pin "P$2") (pinfunction "P$1_P$2") (pintype "bidirectional"))
    )
    (net (code "91") (name "Net-(IC1-CV12)") (class "Default")
      (node (ref "IC1") (pin "P$31") (pinfunction "CV12_P$31") (pintype "bidirectional"))
      (node (ref "R14") (pin "P$2") (pinfunction "P$1_P$2") (pintype "bidirectional"))
    )
    (net (code "92") (name "Net-(IC1-CV13)") (class "Default")
      (node (ref "IC1") (pin "P$27") (pinfunction "CV13_P$27") (pintype "bidirectional"))
      (node (ref "R15") (pin "P$2") (pinfunction "P$1_P$2") (pintype "bidirectional"))
    )
    (net (code "93") (name "Net-(IC1-CV14)") (class "Default")
      (node (ref "IC1") (pin "P$23") (pinfunction "CV14_P$23") (pintype "bidirectional"))
      (node (ref "R16") (pin "P$2") (pinfunction "P$1_P$2") (pintype "bidirectional"))
    )
    (net (code "94") (name "Net-(IC1-CV15)") (class "Default")
      (node (ref "IC1") (pin "P$19") (pinfunction "CV15_P$19") (pintype "bidirectional"))
      (node (ref "R17") (pin "P$2") (pinfunction "P$1_P$2") (pintype "bidirectional"))
    )
    (net (code "95") (name "Net-(IC1-CV16)") (class "Default")
      (node (ref "IC1") (pin "P$15") (pinfunction "CV16_P$15") (pintype "bidirectional"))
      (node (ref "R18") (pin "P$2") (pinfunction "P$1_P$2") (pintype "bidirectional"))
    )
    (net (code "96") (name "Net-(MOS1-D1-PadP$7)") (class "Default")
      (node (ref "MOS1") (pin "P$7") (pinfunction "D1_P$7") (pintype "bidirectional"))
      (node (ref "MOS1") (pin "P$8") (pinfunction "D1_P$8") (pintype "bidirectional"))
      (node (ref "R19") (pin "1") (pinfunction "1_1") (pintype "passive"))
    )
    (net (code "97") (name "Net-(MOS1-D2-PadP$5)") (class "Default")
      (node (ref "MOS1") (pin "P$5") (pinfunction "D2_P$5") (pintype "bidirectional"))
      (node (ref "MOS1") (pin "P$6") (pinfunction "D2_P$6") (pintype "bidirectional"))
      (node (ref "R20") (pin "1") (pinfunction "1_1") (pintype "passive"))
    )
    (net (code "98") (name "Net-(MOS2-D1-PadP$7)") (class "Default")
      (node (ref "MOS2") (pin "P$7") (pinfunction "D1_P$7") (pintype "bidirectional"))
      (node (ref "MOS2") (pin "P$8") (pinfunction "D1_P$8") (pintype "bidirectional"))
      (node (ref "R21") (pin "1") (pinfunction "1_1") (pintype "passive"))
    )
    (net (code "99") (name "Net-(MOS2-D2-PadP$5)") (class "Default")
      (node (ref "MOS2") (pin "P$5") (pinfunction "D2_P$5") (pintype "bidirectional"))
      (node (ref "MOS2") (pin "P$6") (pinfunction "D2_P$6") (pintype "bidirectional"))
      (node (ref "R22") (pin "1") (pinfunction "1_1") (pintype "passive"))
    )
    (net (code "100") (name "Net-(MOS3-D1-PadP$7)") (class "Default")
      (node (ref "MOS3") (pin "P$7") (pinfunction "D1_P$7") (pintype "bidirectional"))
      (node (ref "MOS3") (pin "P$8") (pinfunction "D1_P$8") (pintype "bidirectional"))
      (node (ref "R23") (pin "1") (pinfunction "1_1") (pintype "passive"))
    )
    (net (code "101") (name "Net-(MOS3-D2-PadP$5)") (class "Default")
      (node (ref "MOS3") (pin "P$5") (pinfunction "D2_P$5") (pintype "bidirectional"))
      (node (ref "MOS3") (pin "P$6") (pinfunction "D2_P$6") (pintype "bidirectional"))
      (node (ref "R24") (pin "1") (pinfunction "1_1") (pintype "passive"))
    )
    (net (code "102") (name "Net-(MOS4-D1-PadP$7)") (class "Default")
      (node (ref "MOS4") (pin "P$7") (pinfunction "D1_P$7") (pintype "bidirectional"))
      (node (ref "MOS4") (pin "P$8") (pinfunction "D1_P$8") (pintype "bidirectional"))
      (node (ref "R25") (pin "1") (pinfunction "1_1") (pintype "passive"))
    )
    (net (code "103") (name "Net-(MOS4-D2-PadP$5)") (class "Default")
      (node (ref "MOS4") (pin "P$5") (pinfunction "D2_P$5") (pintype "bidirectional"))
      (node (ref "MOS4") (pin "P$6") (pinfunction "D2_P$6") (pintype "bidirectional"))
      (node (ref "R26") (pin "1") (pinfunction "1_1") (pintype "passive"))
    )
    (net (code "104") (name "Net-(MOS5-D1-PadP$7)") (class "Default")
      (node (ref "MOS5") (pin "P$7") (pinfunction "D1_P$7") (pintype "bidirectional"))
      (node (ref "MOS5") (pin "P$8") (pinfunction "D1_P$8") (pintype "bidirectional"))
      (node (ref "R27") (pin "1") (pinfunction "1_1") (pintype "passive"))
    )
    (net (code "105") (name "Net-(MOS5-D2-PadP$5)") (class "Default")
      (node (ref "MOS5") (pin "P$5") (pinfunction "D2_P$5") (pintype "bidirectional"))
      (node (ref "MOS5") (pin "P$6") (pinfunction "D2_P$6") (pintype "bidirectional"))
      (node (ref "R28") (pin "1") (pinfunction "1_1") (pintype "passive"))
    )
    (net (code "106") (name "Net-(MOS6-D1-PadP$7)") (class "Default")
      (node (ref "MOS6") (pin "P$7") (pinfunction "D1_P$7") (pintype "bidirectional"))
      (node (ref "MOS6") (pin "P$8") (pinfunction "D1_P$8") (pintype "bidirectional"))
      (node (ref "R29") (pin "1") (pinfunction "1_1") (pintype "passive"))
    )
    (net (code "107") (name "Net-(MOS6-D2-PadP$5)") (class "Default")
      (node (ref "MOS6") (pin "P$5") (pinfunction "D2_P$5") (pintype "bidirectional"))
      (node (ref "MOS6") (pin "P$6") (pinfunction "D2_P$6") (pintype "bidirectional"))
      (node (ref "R30") (pin "1") (pinfunction "1_1") (pintype "passive"))
    )
    (net (code "108") (name "Net-(MOS7-D1-PadP$7)") (class "Default")
      (node (ref "MOS7") (pin "P$7") (pinfunction "D1_P$7") (pintype "bidirectional"))
      (node (ref "MOS7") (pin "P$8") (pinfunction "D1_P$8") (pintype "bidirectional"))
      (node (ref "R31") (pin "1") (pinfunction "1_1") (pintype "passive"))
    )
    (net (code "109") (name "Net-(MOS7-D2-PadP$5)") (class "Default")
      (node (ref "MOS7") (pin "P$5") (pinfunction "D2_P$5") (pintype "bidirectional"))
      (node (ref "MOS7") (pin "P$6") (pinfunction "D2_P$6") (pintype "bidirectional"))
      (node (ref "R32") (pin "1") (pinfunction "1_1") (pintype "passive"))
    )
    (net (code "110") (name "Net-(MOS8-D1-PadP$7)") (class "Default")
      (node (ref "MOS8") (pin "P$7") (pinfunction "D1_P$7") (pintype "bidirectional"))
      (node (ref "MOS8") (pin "P$8") (pinfunction "D1_P$8") (pintype "bidirectional"))
      (node (ref "R33") (pin "1") (pinfunction "1_1") (pintype "passive"))
    )
    (net (code "111") (name "Net-(MOS8-D2-PadP$5)") (class "Default")
      (node (ref "MOS8") (pin "P$5") (pinfunction "D2_P$5") (pintype "bidirectional"))
      (node (ref "MOS8") (pin "P$6") (pinfunction "D2_P$6") (pintype "bidirectional"))
      (node (ref "R34") (pin "1") (pinfunction "1_1") (pintype "passive"))
    )
  )
)
